# ACTUATOR_PWR_PROT.net
KiCad netlist of a schematic drawn in Altium Designer
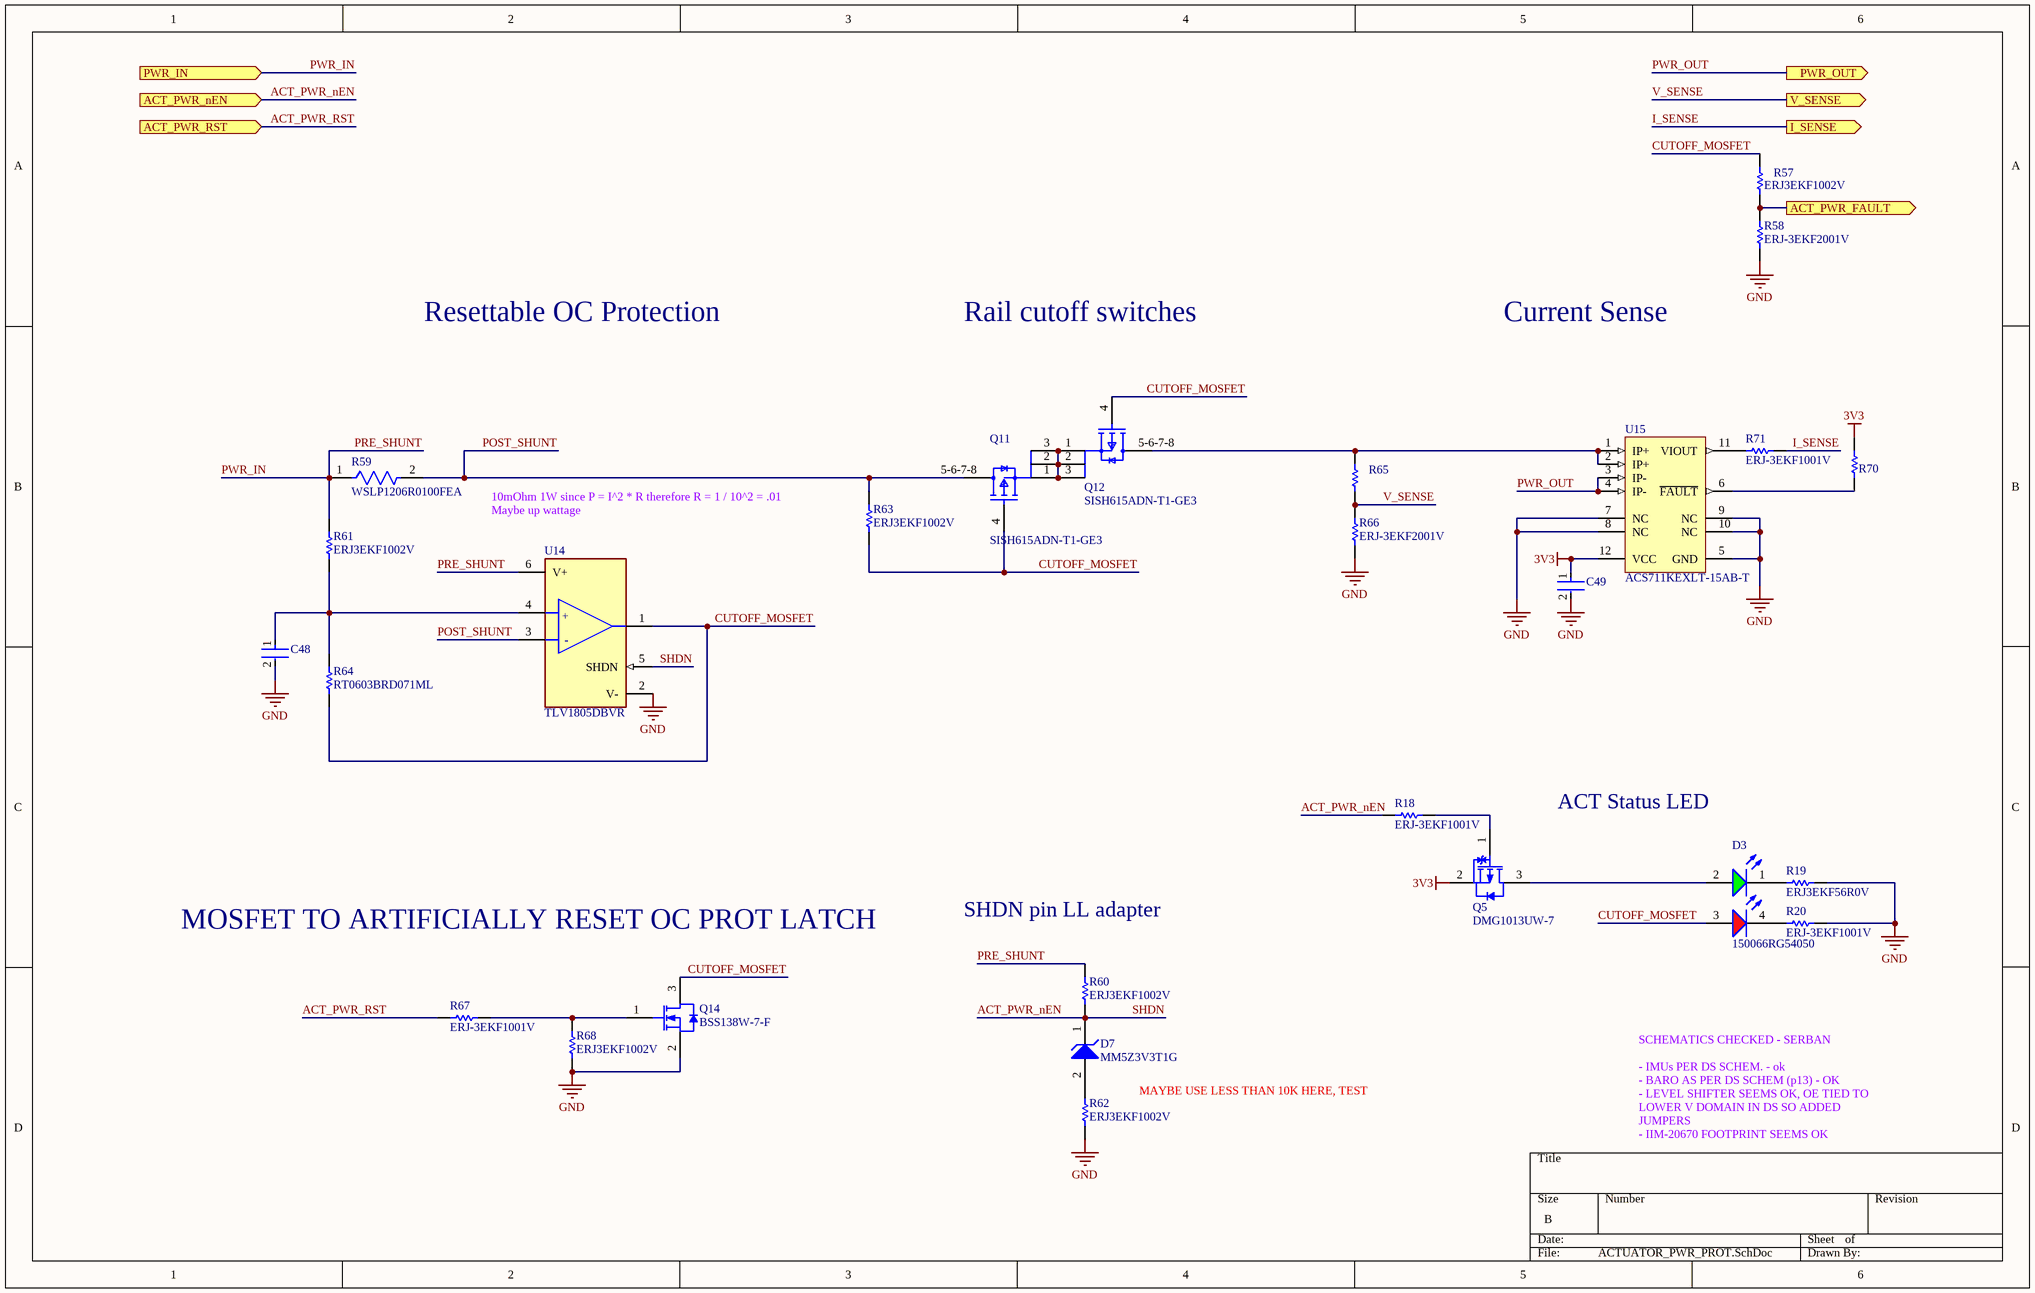
[diagram p0: ACTUATOR_PWR_PROT.SchDoc]

(export (version "E")
  (design (tool "Eeschema 10.0.6"))
  (components
    (comp (ref "C48")
      (value "GRM188R71H104KA93D")
      (footprint "FP-0402-L_1_0_0_05-W_0_5-IPC_A")
      (description "LARGE PADS, 0402 CAP, CHANGE COMMENT TO MATCH REAL P/N")
      (libsource (lib "Space Concordia") (part "b4654b650e69147ec39a6b967a45e02"))
    )
    (comp (ref "C49")
      (value "GRM188R71H104KA93D")
      (footprint "FP-0402-L_1_0_0_05-W_0_5-IPC_A")
      (description "LARGE PADS, 0402 CAP, CHANGE COMMENT TO MATCH REAL P/N")
      (libsource (lib "Space Concordia") (part "b4654b650e69147ec39a6b967a45e02"))
    )
    (comp (ref "D3")
      (value "150066RG54050")
      (footprint "WL-SBCD_0606")
      (description "Led, Red/Grn, 180Mcd/230Mcd, 624Nm/525Nm Rohs Compliant: Yes")
      (libsource (lib "uORocketry Hardware") (part "WL-SBCD_0606_Red & Green"))
    )
    (comp (ref "D7")
      (value "MM5Z3V3T1G")
      (footprint "ONSC-SOD-523-2-502-01_V")
      (description "Zener Voltage Regulator, 500 mW, 2-Pin SOD-523, Pb-Free, Tape and Reel")
      (fields (field (name "MANUFACTURER") "On Semiconductor"))
      (libsource (lib "Altium Content Vault") (part "ONSC-K1A2-2"))
    )
    (comp (ref "Q5")
      (value "DMG1013UW-7")
      (footprint "DIOD-SOT323-3_V")
      (fields (field (name "MANUFACTURER") "Diodes Inc"))
      (libsource (lib "Altium Content Vault") (part "PEMOS-GSD-3_C"))
    )
    (comp (ref "Q11")
      (value "SISH615ADN-T1-GE3")
      (footprint "SISH615ADN-T1-GE3-Footprint-1")
      (description "Trans MOSFET P-CH 20V 22.1A 8-Pin PowerPAK 1212 EP T/R")
      (libsource (lib "Space Concordia") (part "CMP-013-00036-4"))
    )
    (comp (ref "Q12")
      (value "SISH615ADN-T1-GE3")
      (footprint "SISH615ADN-T1-GE3-Footprint-1")
      (description "Trans MOSFET P-CH 20V 22.1A 8-Pin PowerPAK 1212 EP T/R")
      (libsource (lib "Space Concordia") (part "CMP-013-00036-4"))
    )
    (comp (ref "Q14")
      (value "BSS138W-7-F")
      (footprint "DIOD-SOT323-3_V")
      (fields (field (name "MANUFACTURER") "DiodesIncorporated"))
      (libsource (lib "Altium Content Vault") (part "NEMOS-GSD-3"))
    )
    (comp (ref "R18")
      (value "ERJ-3EKF1001V")
      (footprint "RESC1608X55X30LL15T15")
      (fields (field (name "MANUFACTURER") "Panasonic"))
      (libsource (lib "Altium Content Vault") (part "RES"))
    )
    (comp (ref "R19")
      (value "ERJ3EKF56R0V")
      (footprint "RESC1608X55X30NL15T15")
      (fields (field (name "MANUFACTURER") "Panasonic"))
      (libsource (lib "Altium Content Vault") (part "RES"))
    )
    (comp (ref "R20")
      (value "ERJ-3EKF1001V")
      (footprint "RESC1608X55X30LL15T15")
      (fields (field (name "MANUFACTURER") "Panasonic"))
      (libsource (lib "Altium Content Vault") (part "RES"))
    )
    (comp (ref "R57")
      (value "ERJ3EKF1002V")
      (footprint "RESC1609X55X30LL15T15")
      (description "Chip Resistor, 10 KOhm, +/- 1%, 0.1 W, -55 to 155 degC, 0603 (1608 Metric), RoHS, Tape and Reel")
      (fields (field (name "TOLERANCE") "1%") (field (name "MANUFACTURER") "Panasonic"))
      (libsource (lib "Altium Content Vault") (part "RES-2"))
    )
    (comp (ref "R58")
      (value "ERJ-3EKF2001V")
      (footprint "RESC1608X55X30ML15T15")
      (fields (field (name "MANUFACTURER") "Panasonic"))
      (libsource (lib "Altium Content Vault") (part "RES"))
    )
    (comp (ref "R59")
      (value "WSLP1206R0100FEA")
      (footprint "FP-WSLP1206-FP_1_65x1_93x-MFG")
      (description "RES 0.01 OHM 1% 1W 1206")
      (fields (field (name "TOLERANCE") "1%"))
      (libsource (lib "Altium Content Vault") (part "1029c3af85768c4190bb7ad29bc67b5"))
    )
    (comp (ref "R60")
      (value "ERJ3EKF1002V")
      (footprint "RESC1609X55X30LL15T15")
      (description "Chip Resistor, 10 KOhm, +/- 1%, 0.1 W, -55 to 155 degC, 0603 (1608 Metric), RoHS, Tape and Reel")
      (fields (field (name "TOLERANCE") "1%") (field (name "MANUFACTURER") "Panasonic"))
      (libsource (lib "Altium Content Vault") (part "RES-2"))
    )
    (comp (ref "R61")
      (value "ERJ3EKF1002V")
      (footprint "RESC1609X55X30LL15T15")
      (description "Chip Resistor, 10 KOhm, +/- 1%, 0.1 W, -55 to 155 degC, 0603 (1608 Metric), RoHS, Tape and Reel")
      (fields (field (name "TOLERANCE") "1%") (field (name "MANUFACTURER") "Panasonic"))
      (libsource (lib "Altium Content Vault") (part "RES-2"))
    )
    (comp (ref "R62")
      (value "ERJ3EKF1002V")
      (footprint "RESC1609X55X30LL15T15")
      (description "Chip Resistor, 10 KOhm, +/- 1%, 0.1 W, -55 to 155 degC, 0603 (1608 Metric), RoHS, Tape and Reel")
      (fields (field (name "TOLERANCE") "1%") (field (name "MANUFACTURER") "Panasonic"))
      (libsource (lib "Altium Content Vault") (part "RES-2"))
    )
    (comp (ref "R63")
      (value "ERJ3EKF1002V")
      (footprint "RESC1609X55X30LL15T15")
      (description "Chip Resistor, 10 KOhm, +/- 1%, 0.1 W, -55 to 155 degC, 0603 (1608 Metric), RoHS, Tape and Reel")
      (fields (field (name "TOLERANCE") "1%") (field (name "MANUFACTURER") "Panasonic"))
      (libsource (lib "Altium Content Vault") (part "RES-2"))
    )
    (comp (ref "R64")
      (value "RT0603BRD071ML")
      (footprint "RESC1608X55X30NL20T20")
      (fields (field (name "MANUFACTURER") "Panasonic") (field (name "PART NUMBER") "ERA-3AEB163V"))
      (libsource (lib "Altium Content Vault") (part "RES"))
    )
    (comp (ref "R65")
      (value "ERJ3EKF1002V")
      (footprint "RESC1609X55X30LL15T15")
      (description "Chip Resistor, 10 KOhm, +/- 1%, 0.1 W, -55 to 155 degC, 0603 (1608 Metric), RoHS, Tape and Reel")
      (fields (field (name "TOLERANCE") "1%") (field (name "MANUFACTURER") "Panasonic"))
      (libsource (lib "Altium Content Vault") (part "RES-2"))
    )
    (comp (ref "R66")
      (value "ERJ-3EKF2001V")
      (footprint "RESC1608X55X30ML15T15")
      (fields (field (name "MANUFACTURER") "Panasonic"))
      (libsource (lib "Altium Content Vault") (part "RES"))
    )
    (comp (ref "R67")
      (value "ERJ-3EKF1001V")
      (footprint "RESC1608X55X30LL15T15")
      (fields (field (name "MANUFACTURER") "Panasonic"))
      (libsource (lib "Altium Content Vault") (part "RES"))
    )
    (comp (ref "R68")
      (value "ERJ3EKF1002V")
      (footprint "RESC1609X55X30LL15T15")
      (description "Chip Resistor, 10 KOhm, +/- 1%, 0.1 W, -55 to 155 degC, 0603 (1608 Metric), RoHS, Tape and Reel")
      (fields (field (name "TOLERANCE") "1%") (field (name "MANUFACTURER") "Panasonic"))
      (libsource (lib "Altium Content Vault") (part "RES-2"))
    )
    (comp (ref "R70")
      (value "ERJ3EKF1002V")
      (footprint "RESC1609X55X30LL15T15")
      (description "Chip Resistor, 10 KOhm, +/- 1%, 0.1 W, -55 to 155 degC, 0603 (1608 Metric), RoHS, Tape and Reel")
      (fields (field (name "TOLERANCE") "1%") (field (name "MANUFACTURER") "Panasonic"))
      (libsource (lib "Altium Content Vault") (part "RES-2"))
    )
    (comp (ref "R71")
      (value "ERJ-3EKF1001V")
      (footprint "RESC1608X55X30LL15T15")
      (fields (field (name "MANUFACTURER") "Panasonic"))
      (libsource (lib "Altium Content Vault") (part "RES"))
    )
    (comp (ref "U14")
      (value "TLV1805DBVR")
      (footprint "FP-DBV0006A-IPC_C")
      (description "40V, RAIL-TO-RAIL INPUT, PUSH-PU")
      (libsource (lib "Altium Content Vault") (part "c7aa3bc3dbf0dc8b0b0354779bd1228"))
    )
    (comp (ref "U15")
      (value "ACS711KEXLT-15AB-T")
      (footprint "ALEG-EX-12_V")
      (libsource (lib "Altium Content Vault") (part "ALEG-ACS711-QFN-12"))
    )
  )
  (nets
    (net (code "1") (name "/ACT_PWR_FAULT") (class "Default")
      (node (ref "R57") (pin "2") (pinfunction "2_2") (pintype "passive"))
      (node (ref "R58") (pin "2") (pinfunction "2_2") (pintype "passive"))
    )
    (net (code "2") (name "/ACT_PWR_RST") (class "Default")
      (node (ref "R67") (pin "2") (pinfunction "2_2") (pintype "passive"))
    )
    (net (code "3") (name "/ACT_PWR_nEN") (class "Default")
      (node (ref "D7") (pin "1") (pinfunction "K_1") (pintype "passive"))
      (node (ref "R18") (pin "1") (pinfunction "1_1") (pintype "passive"))
      (node (ref "R60") (pin "1") (pinfunction "1_1") (pintype "passive"))
      (node (ref "U14") (pin "5") (pinfunction "SHDN_5") (pintype "input"))
    )
    (net (code "4") (name "/CUTOFF_MOSFET") (class "Default")
      (node (ref "D3") (pin "3") (pinfunction "A_3") (pintype "passive"))
      (node (ref "Q11") (pin "4") (pinfunction "G_4") (pintype "passive"))
      (node (ref "Q12") (pin "4") (pinfunction "G_4") (pintype "passive"))
      (node (ref "Q14") (pin "3") (pinfunction "D_3") (pintype "passive"))
      (node (ref "R57") (pin "1") (pinfunction "1_1") (pintype "passive"))
      (node (ref "R63") (pin "1") (pinfunction "1_1") (pintype "passive"))
      (node (ref "R64") (pin "1") (pinfunction "1_1") (pintype "passive"))
      (node (ref "U14") (pin "1") (pinfunction "OUT_1") (pintype "passive"))
    )
    (net (code "5") (name "/I_SENSE") (class "Default")
      (node (ref "R71") (pin "2") (pinfunction "2_2") (pintype "passive"))
    )
    (net (code "6") (name "/POST_SHUNT") (class "Default")
      (node (ref "Q11") (pin "5-6-7-8") (pinfunction "D_5-6-7-8") (pintype "passive"))
      (node (ref "R59") (pin "2") (pinfunction "2_2") (pintype "passive"))
      (node (ref "R63") (pin "2") (pinfunction "2_2") (pintype "passive"))
      (node (ref "U14") (pin "3") (pinfunction "-IN_3") (pintype "tri_state"))
    )
    (net (code "7") (name "/PRE_SHUNT") (class "Default")
      (node (ref "R59") (pin "1") (pinfunction "1_1") (pintype "passive"))
      (node (ref "R60") (pin "2") (pinfunction "2_2") (pintype "passive"))
      (node (ref "R61") (pin "2") (pinfunction "2_2") (pintype "passive"))
      (node (ref "U14") (pin "6") (pinfunction "V+_6") (pintype "power_in"))
    )
    (net (code "8") (name "/PWR_OUT") (class "Default")
      (node (ref "U15") (pin "3") (pinfunction "IP-_3") (pintype "input"))
      (node (ref "U15") (pin "4") (pinfunction "IP-_4") (pintype "input"))
    )
    (net (code "9") (name "/V_SENSE") (class "Default")
      (node (ref "R65") (pin "2") (pinfunction "2_2") (pintype "passive"))
      (node (ref "R66") (pin "2") (pinfunction "2_2") (pintype "passive"))
    )
    (net (code "10") (name "3V3") (class "Default")
      (node (ref "C49") (pin "1") (pinfunction "1_1") (pintype "passive"))
      (node (ref "Q5") (pin "2") (pinfunction "S_2") (pintype "passive"))
      (node (ref "R70") (pin "2") (pinfunction "2_2") (pintype "passive"))
      (node (ref "U15") (pin "12") (pinfunction "VCC_12") (pintype "power_in"))
    )
    (net (code "11") (name "GND") (class "Default")
      (node (ref "C48") (pin "2") (pinfunction "2_2") (pintype "passive"))
      (node (ref "C49") (pin "2") (pinfunction "2_2") (pintype "passive"))
      (node (ref "Q14") (pin "2") (pinfunction "S_2") (pintype "passive"))
      (node (ref "R19") (pin "1") (pinfunction "1_1") (pintype "passive"))
      (node (ref "R20") (pin "2") (pinfunction "2_2") (pintype "passive"))
      (node (ref "R58") (pin "1") (pinfunction "1_1") (pintype "passive"))
      (node (ref "R62") (pin "1") (pinfunction "1_1") (pintype "passive"))
      (node (ref "R66") (pin "1") (pinfunction "1_1") (pintype "passive"))
      (node (ref "R68") (pin "1") (pinfunction "1_1") (pintype "passive"))
      (node (ref "U14") (pin "2") (pinfunction "V-_2") (pintype "power_in"))
      (node (ref "U15") (pin "10") (pinfunction "NC_10") (pintype "passive"))
      (node (ref "U15") (pin "5") (pinfunction "GND_5") (pintype "power_in"))
      (node (ref "U15") (pin "7") (pinfunction "NC_7") (pintype "passive"))
      (node (ref "U15") (pin "8") (pinfunction "NC_8") (pintype "passive"))
      (node (ref "U15") (pin "9") (pinfunction "NC_9") (pintype "passive"))
    )
    (net (code "12") (name "Net-(D3-K-Pad1)") (class "Default")
      (node (ref "D3") (pin "1") (pinfunction "K_1") (pintype "passive"))
      (node (ref "R19") (pin "2") (pinfunction "2_2") (pintype "passive"))
    )
    (net (code "13") (name "Net-(D3-K-Pad4)") (class "Default")
      (node (ref "D3") (pin "4") (pinfunction "K_4") (pintype "passive"))
      (node (ref "R20") (pin "1") (pinfunction "1_1") (pintype "passive"))
    )
    (net (code "14") (name "Net-(D7-A)") (class "Default")
      (node (ref "D7") (pin "2") (pinfunction "A_2") (pintype "passive"))
      (node (ref "R62") (pin "2") (pinfunction "2_2") (pintype "passive"))
    )
    (net (code "15") (name "Net-(Q5-D)") (class "Default")
      (node (ref "D3") (pin "2") (pinfunction "A_2") (pintype "passive"))
      (node (ref "Q5") (pin "3") (pinfunction "D_3") (pintype "passive"))
    )
    (net (code "16") (name "Net-(Q5-G)") (class "Default")
      (node (ref "Q5") (pin "1") (pinfunction "G_1") (pintype "passive"))
      (node (ref "R18") (pin "2") (pinfunction "2_2") (pintype "passive"))
    )
    (net (code "17") (name "Net-(Q11-S-Pad1)") (class "Default")
      (node (ref "Q11") (pin "1") (pinfunction "S_1") (pintype "passive"))
      (node (ref "Q11") (pin "2") (pinfunction "S_2") (pintype "passive"))
      (node (ref "Q11") (pin "3") (pinfunction "S_3") (pintype "passive"))
      (node (ref "Q12") (pin "1") (pinfunction "S_1") (pintype "passive"))
      (node (ref "Q12") (pin "2") (pinfunction "S_2") (pintype "passive"))
      (node (ref "Q12") (pin "3") (pinfunction "S_3") (pintype "passive"))
    )
    (net (code "18") (name "Net-(Q12-D)") (class "Default")
      (node (ref "Q12") (pin "5-6-7-8") (pinfunction "D_5-6-7-8") (pintype "passive"))
      (node (ref "R65") (pin "1") (pinfunction "1_1") (pintype "passive"))
      (node (ref "U15") (pin "1") (pinfunction "IP+_1") (pintype "input"))
      (node (ref "U15") (pin "2") (pinfunction "IP+_2") (pintype "input"))
    )
    (net (code "19") (name "Net-(Q14-G)") (class "Default")
      (node (ref "Q14") (pin "1") (pinfunction "G_1") (pintype "passive"))
      (node (ref "R67") (pin "1") (pinfunction "1_1") (pintype "passive"))
      (node (ref "R68") (pin "2") (pinfunction "2_2") (pintype "passive"))
    )
    (net (code "20") (name "Net-(U14-+IN)") (class "Default")
      (node (ref "C48") (pin "1") (pinfunction "1_1") (pintype "passive"))
      (node (ref "R61") (pin "1") (pinfunction "1_1") (pintype "passive"))
      (node (ref "R64") (pin "2") (pinfunction "2_2") (pintype "passive"))
      (node (ref "U14") (pin "4") (pinfunction "+IN_4") (pintype "tri_state"))
    )
    (net (code "21") (name "Net-(U15-VIOUT)") (class "Default")
      (node (ref "R71") (pin "1") (pinfunction "1_1") (pintype "passive"))
      (node (ref "U15") (pin "11") (pinfunction "VIOUT_11") (pintype "output"))
    )
    (net (code "22") (name "Net-(U15-~{FAULT})") (class "Default")
      (node (ref "R70") (pin "1") (pinfunction "1_1") (pintype "passive"))
      (node (ref "U15") (pin "6") (pinfunction "~{FAULT}_6") (pintype "output"))
    )
  )
)
